# VCA.net
KiCad netlist of a schematic drawn in Altium Designer
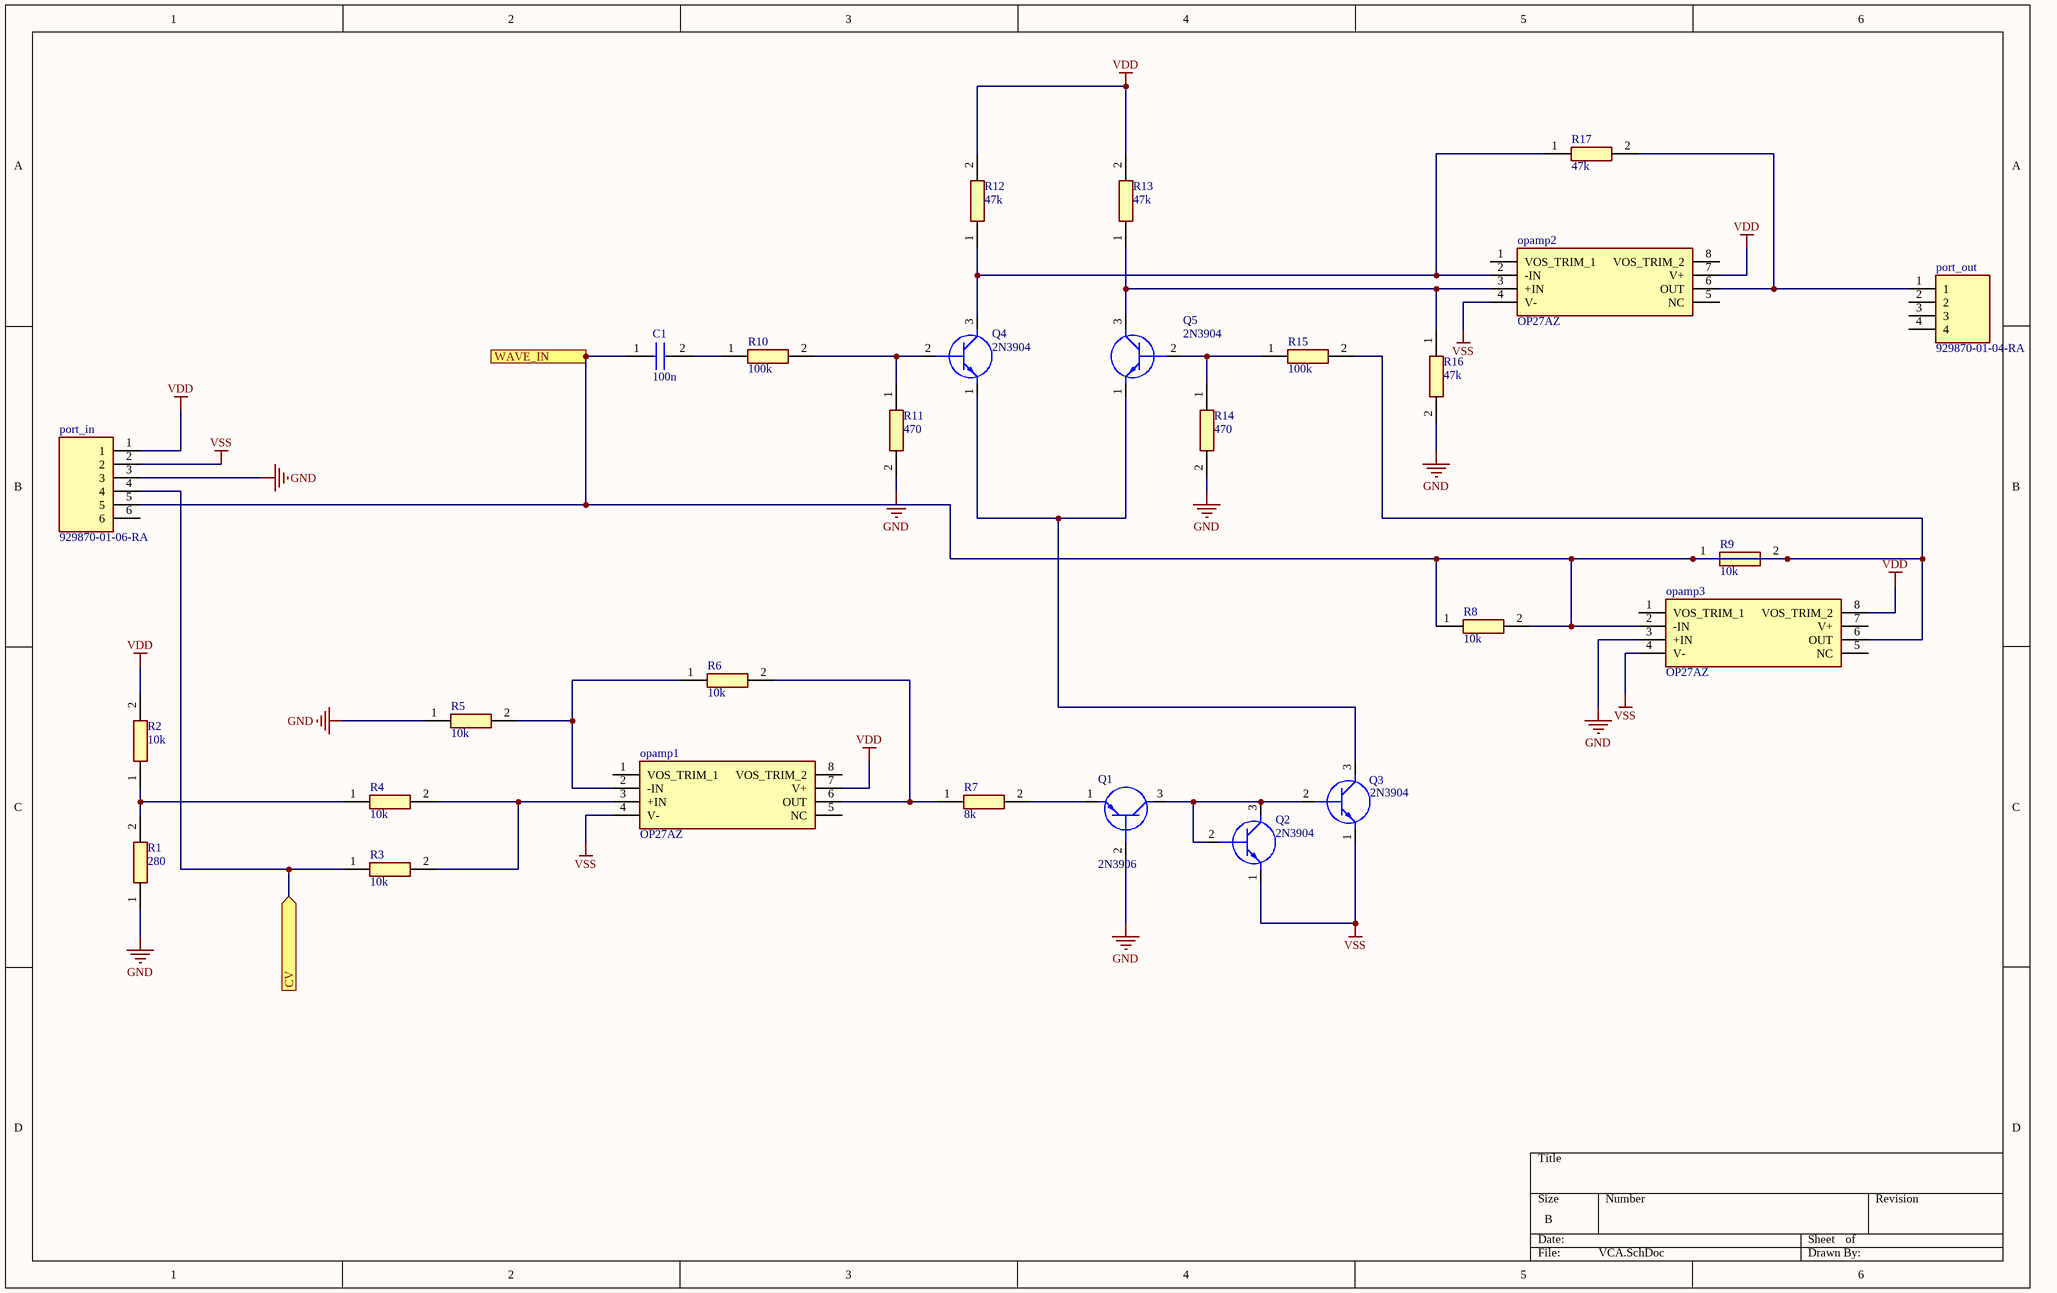
[diagram p0: VCA.SchDoc]

(export (version "E")
  (design (tool "Eeschema 10.0.6"))
  (components
    (comp (ref "C1")
      (value "100n")
      (footprint "SamacSys:CAPPA2400W30L800D400")
      (description "Capacitor")
      (fields (field (name "MANUFACTURER_PART_NUMBER") "0113207"))
      (libsource (lib "SamacSys") (part "0113207"))
    )
    (comp (ref "opamp1")
      (value "OP27AZ")
      (footprint "SamacSys:DIP775W58P254L1029H508Q8N")
      (description "Integrated Circuit")
      (fields (field (name "MOUSER PART NUMBER") "700-OP27AZNR"))
      (libsource (lib "SamacSys") (part "OP27AZ"))
    )
    (comp (ref "opamp2")
      (value "OP27AZ")
      (footprint "SamacSys:DIP775W58P254L1029H508Q8N")
      (description "Integrated Circuit")
      (fields (field (name "MOUSER PART NUMBER") "700-OP27AZNR"))
      (libsource (lib "SamacSys") (part "OP27AZ"))
    )
    (comp (ref "opamp3")
      (value "OP27AZ")
      (footprint "SamacSys:DIP775W58P254L1029H508Q8N")
      (description "Integrated Circuit")
      (fields (field (name "MOUSER PART NUMBER") "700-OP27AZNR"))
      (libsource (lib "SamacSys") (part "OP27AZ"))
    )
    (comp (ref "port_in")
      (value "929870-01-06-RA")
      (footprint "SamacSys:RHDR6W64P0X254_1X6_1524X254X380P")
      (description "Connector")
      (fields (field (name "MOUSER PART NUMBER") "517-929870-01-06-RA"))
      (libsource (lib "SamacSys") (part "929870-01-06-RA"))
    )
    (comp (ref "port_out")
      (value "929870-01-04-RA")
      (footprint "SamacSys:RHDR4W76P0X254_1X4_1016X254X826P")
      (description "Connector")
      (fields (field (name "MOUSER PART NUMBER") "517-929870-01-04-RA"))
      (libsource (lib "SamacSys") (part "929870-01-04-RA"))
    )
    (comp (ref "Q1")
      (value "2N3906")
      (footprint "SamacSys:2N5457")
      (description "Transistor BJT PNP")
      (fields (field (name "MOUSER PART NUMBER") "610-2N3906"))
      (libsource (lib "SamacSys") (part "2N3906"))
    )
    (comp (ref "Q2")
      (value "2N3904")
      (footprint "SamacSys:CS_TO-92")
      (description "Transistor BJT NPN")
      (fields (field (name "MOUSER PART NUMBER") "610-2N3904"))
      (libsource (lib "SamacSys") (part "2N3904"))
    )
    (comp (ref "Q3")
      (value "2N3904")
      (footprint "SamacSys:CS_TO-92")
      (description "Transistor BJT NPN")
      (fields (field (name "MOUSER PART NUMBER") "610-2N3904"))
      (libsource (lib "SamacSys") (part "2N3904"))
    )
    (comp (ref "Q4")
      (value "2N3904")
      (footprint "SamacSys:CS_TO-92")
      (description "Transistor BJT NPN")
      (fields (field (name "MOUSER PART NUMBER") "610-2N3904"))
      (libsource (lib "SamacSys") (part "2N3904"))
    )
    (comp (ref "Q5")
      (value "2N3904")
      (footprint "SamacSys:CS_TO-92")
      (description "Transistor BJT NPN")
      (fields (field (name "MOUSER PART NUMBER") "610-2N3904"))
      (libsource (lib "SamacSys") (part "2N3904"))
    )
    (comp (ref "R1")
      (value "280")
      (footprint "SamacSys:RESAD1650W60L650D250")
      (description "Resistor")
      (fields
        (field (name "MANUFACTURER_PART_NUMBER") "MRS25000C1003FC100")
        (field (name "MOUSER PART NUMBER") "594-MRS25000C1003FC1")
      )
      (libsource (lib "") (part "MRS25000C1003FC100_2"))
    )
    (comp (ref "R2")
      (value "10k")
      (footprint "SamacSys:RESAD1650W60L650D250")
      (description "Resistor")
      (fields
        (field (name "MANUFACTURER_PART_NUMBER") "MRS25000C1003FC100")
        (field (name "MOUSER PART NUMBER") "594-MRS25000C1003FC1")
      )
      (libsource (lib "") (part "MRS25000C1003FC100_2"))
    )
    (comp (ref "R3")
      (value "10k")
      (footprint "SamacSys:RESAD1650W60L650D250")
      (description "Resistor")
      (fields
        (field (name "MANUFACTURER_PART_NUMBER") "MRS25000C1003FC100")
        (field (name "MOUSER PART NUMBER") "594-MRS25000C1003FC1")
      )
      (libsource (lib "SamacSys") (part "MRS25000C1003FC100"))
    )
    (comp (ref "R4")
      (value "10k")
      (footprint "SamacSys:RESAD1650W60L650D250")
      (description "Resistor")
      (fields
        (field (name "MANUFACTURER_PART_NUMBER") "MRS25000C1003FC100")
        (field (name "MOUSER PART NUMBER") "594-MRS25000C1003FC1")
      )
      (libsource (lib "SamacSys") (part "MRS25000C1003FC100"))
    )
    (comp (ref "R5")
      (value "10k")
      (footprint "SamacSys:RESAD1650W60L650D250")
      (description "Resistor")
      (fields
        (field (name "MANUFACTURER_PART_NUMBER") "MRS25000C1003FC100")
        (field (name "MOUSER PART NUMBER") "594-MRS25000C1003FC1")
      )
      (libsource (lib "SamacSys") (part "MRS25000C1003FC100"))
    )
    (comp (ref "R6")
      (value "10k")
      (footprint "SamacSys:RESAD1650W60L650D250")
      (description "Resistor")
      (fields
        (field (name "MANUFACTURER_PART_NUMBER") "MRS25000C1003FC100")
        (field (name "MOUSER PART NUMBER") "594-MRS25000C1003FC1")
      )
      (libsource (lib "SamacSys") (part "MRS25000C1003FC100"))
    )
    (comp (ref "R7")
      (value "8k")
      (footprint "SamacSys:RESAD1650W60L650D250")
      (description "Resistor")
      (fields
        (field (name "MANUFACTURER_PART_NUMBER") "MRS25000C1003FC100")
        (field (name "MOUSER PART NUMBER") "594-MRS25000C1003FC1")
      )
      (libsource (lib "SamacSys") (part "MRS25000C1003FC100"))
    )
    (comp (ref "R8")
      (value "10k")
      (footprint "SamacSys:RESAD1650W60L650D250")
      (description "Resistor")
      (fields
        (field (name "MANUFACTURER_PART_NUMBER") "MRS25000C1003FC100")
        (field (name "MOUSER PART NUMBER") "594-MRS25000C1003FC1")
      )
      (libsource (lib "SamacSys") (part "MRS25000C1003FC100"))
    )
    (comp (ref "R9")
      (value "10k")
      (footprint "SamacSys:RESAD1650W60L650D250")
      (description "Resistor")
      (fields
        (field (name "MANUFACTURER_PART_NUMBER") "MRS25000C1003FC100")
        (field (name "MOUSER PART NUMBER") "594-MRS25000C1003FC1")
      )
      (libsource (lib "SamacSys") (part "MRS25000C1003FC100"))
    )
    (comp (ref "R10")
      (value "100k")
      (footprint "SamacSys:RESAD1650W60L650D250")
      (description "Resistor")
      (fields
        (field (name "MANUFACTURER_PART_NUMBER") "MRS25000C1003FC100")
        (field (name "MOUSER PART NUMBER") "594-MRS25000C1003FC1")
      )
      (libsource (lib "SamacSys") (part "MRS25000C1003FC100"))
    )
    (comp (ref "R11")
      (value "470")
      (footprint "SamacSys:RESAD1650W60L650D250")
      (description "Resistor")
      (fields
        (field (name "MANUFACTURER_PART_NUMBER") "MRS25000C1003FC100")
        (field (name "MOUSER PART NUMBER") "594-MRS25000C1003FC1")
      )
      (libsource (lib "") (part "MRS25000C1003FC100_1"))
    )
    (comp (ref "R12")
      (value "47k")
      (footprint "SamacSys:RESAD1650W60L650D250")
      (description "Resistor")
      (fields
        (field (name "MANUFACTURER_PART_NUMBER") "MRS25000C1003FC100")
        (field (name "MOUSER PART NUMBER") "594-MRS25000C1003FC1")
      )
      (libsource (lib "") (part "MRS25000C1003FC100_2"))
    )
    (comp (ref "R13")
      (value "47k")
      (footprint "SamacSys:RESAD1650W60L650D250")
      (description "Resistor")
      (fields
        (field (name "MANUFACTURER_PART_NUMBER") "MRS25000C1003FC100")
        (field (name "MOUSER PART NUMBER") "594-MRS25000C1003FC1")
      )
      (libsource (lib "") (part "MRS25000C1003FC100_2"))
    )
    (comp (ref "R14")
      (value "470")
      (footprint "SamacSys:RESAD1650W60L650D250")
      (description "Resistor")
      (fields
        (field (name "MANUFACTURER_PART_NUMBER") "MRS25000C1003FC100")
        (field (name "MOUSER PART NUMBER") "594-MRS25000C1003FC1")
      )
      (libsource (lib "") (part "MRS25000C1003FC100_1"))
    )
    (comp (ref "R15")
      (value "100k")
      (footprint "SamacSys:RESAD1650W60L650D250")
      (description "Resistor")
      (fields
        (field (name "MANUFACTURER_PART_NUMBER") "MRS25000C1003FC100")
        (field (name "MOUSER PART NUMBER") "594-MRS25000C1003FC1")
      )
      (libsource (lib "SamacSys") (part "MRS25000C1003FC100"))
    )
    (comp (ref "R16")
      (value "47k")
      (footprint "SamacSys:RESAD1650W60L650D250")
      (description "Resistor")
      (fields
        (field (name "MANUFACTURER_PART_NUMBER") "MRS25000C1003FC100")
        (field (name "MOUSER PART NUMBER") "594-MRS25000C1003FC1")
      )
      (libsource (lib "") (part "MRS25000C1003FC100_1"))
    )
    (comp (ref "R17")
      (value "47k")
      (footprint "SamacSys:RESAD1650W60L650D250")
      (description "Resistor")
      (fields
        (field (name "MANUFACTURER_PART_NUMBER") "MRS25000C1003FC100")
        (field (name "MOUSER PART NUMBER") "594-MRS25000C1003FC1")
      )
      (libsource (lib "SamacSys") (part "MRS25000C1003FC100"))
    )
  )
  (nets
    (net (code "1") (name "/CV") (class "Default")
      (node (ref "R3") (pin "1") (pinfunction "1_1") (pintype "passive"))
      (node (ref "port_in") (pin "4") (pinfunction "4_4") (pintype "passive"))
    )
    (net (code "2") (name "/WAVE_IN") (class "Default")
      (node (ref "C1") (pin "1") (pinfunction "+_1") (pintype "passive"))
      (node (ref "R15") (pin "2") (pinfunction "2_2") (pintype "passive"))
      (node (ref "R8") (pin "1") (pinfunction "1_1") (pintype "passive"))
      (node (ref "R8") (pin "2") (pinfunction "2_2") (pintype "passive"))
      (node (ref "R9") (pin "1") (pinfunction "1_1") (pintype "passive"))
      (node (ref "R9") (pin "2") (pinfunction "2_2") (pintype "passive"))
      (node (ref "opamp3") (pin "2") (pinfunction "-IN_2") (pintype "passive"))
      (node (ref "opamp3") (pin "6") (pinfunction "OUT_6") (pintype "passive"))
      (node (ref "port_in") (pin "5") (pinfunction "5_5") (pintype "passive"))
    )
    (net (code "3") (name "GND") (class "Default")
      (node (ref "Q1") (pin "2") (pinfunction "B_2") (pintype "passive"))
      (node (ref "R1") (pin "1") (pinfunction "1_1") (pintype "passive"))
      (node (ref "R11") (pin "2") (pinfunction "2_2") (pintype "passive"))
      (node (ref "R14") (pin "2") (pinfunction "2_2") (pintype "passive"))
      (node (ref "R16") (pin "2") (pinfunction "2_2") (pintype "passive"))
      (node (ref "R5") (pin "1") (pinfunction "1_1") (pintype "passive"))
      (node (ref "opamp3") (pin "3") (pinfunction "+IN_3") (pintype "passive"))
      (node (ref "port_in") (pin "3") (pinfunction "3_3") (pintype "passive"))
    )
    (net (code "4") (name "Net-(C1--)") (class "Default")
      (node (ref "C1") (pin "2") (pinfunction "-_2") (pintype "passive"))
      (node (ref "R10") (pin "1") (pinfunction "1_1") (pintype "passive"))
    )
    (net (code "5") (name "Net-(Q1-C)") (class "Default")
      (node (ref "Q1") (pin "3") (pinfunction "C_3") (pintype "passive"))
      (node (ref "Q2") (pin "2") (pinfunction "B_2") (pintype "passive"))
      (node (ref "Q2") (pin "3") (pinfunction "C_3") (pintype "passive"))
      (node (ref "Q3") (pin "2") (pinfunction "B_2") (pintype "passive"))
    )
    (net (code "6") (name "Net-(Q1-E)") (class "Default")
      (node (ref "Q1") (pin "1") (pinfunction "E_1") (pintype "passive"))
      (node (ref "R7") (pin "2") (pinfunction "2_2") (pintype "passive"))
    )
    (net (code "7") (name "Net-(Q3-C)") (class "Default")
      (node (ref "Q3") (pin "3") (pinfunction "C_3") (pintype "passive"))
      (node (ref "Q4") (pin "1") (pinfunction "E_1") (pintype "passive"))
      (node (ref "Q5") (pin "1") (pinfunction "E_1") (pintype "passive"))
    )
    (net (code "8") (name "Net-(Q4-B)") (class "Default")
      (node (ref "Q4") (pin "2") (pinfunction "B_2") (pintype "passive"))
      (node (ref "R10") (pin "2") (pinfunction "2_2") (pintype "passive"))
      (node (ref "R11") (pin "1") (pinfunction "1_1") (pintype "passive"))
    )
    (net (code "9") (name "Net-(Q4-C)") (class "Default")
      (node (ref "Q4") (pin "3") (pinfunction "C_3") (pintype "passive"))
      (node (ref "R12") (pin "1") (pinfunction "1_1") (pintype "passive"))
      (node (ref "R17") (pin "1") (pinfunction "1_1") (pintype "passive"))
      (node (ref "opamp2") (pin "2") (pinfunction "-IN_2") (pintype "passive"))
    )
    (net (code "10") (name "Net-(Q5-B)") (class "Default")
      (node (ref "Q5") (pin "2") (pinfunction "B_2") (pintype "passive"))
      (node (ref "R14") (pin "1") (pinfunction "1_1") (pintype "passive"))
      (node (ref "R15") (pin "1") (pinfunction "1_1") (pintype "passive"))
    )
    (net (code "11") (name "Net-(Q5-C)") (class "Default")
      (node (ref "Q5") (pin "3") (pinfunction "C_3") (pintype "passive"))
      (node (ref "R13") (pin "1") (pinfunction "1_1") (pintype "passive"))
      (node (ref "R16") (pin "1") (pinfunction "1_1") (pintype "passive"))
      (node (ref "opamp2") (pin "3") (pinfunction "+IN_3") (pintype "passive"))
    )
    (net (code "12") (name "Net-(R1-Pad2)") (class "Default")
      (node (ref "R1") (pin "2") (pinfunction "2_2") (pintype "passive"))
      (node (ref "R2") (pin "1") (pinfunction "1_1") (pintype "passive"))
      (node (ref "R4") (pin "1") (pinfunction "1_1") (pintype "passive"))
    )
    (net (code "13") (name "Net-(opamp1-+IN)") (class "Default")
      (node (ref "R3") (pin "2") (pinfunction "2_2") (pintype "passive"))
      (node (ref "R4") (pin "2") (pinfunction "2_2") (pintype "passive"))
      (node (ref "opamp1") (pin "3") (pinfunction "+IN_3") (pintype "passive"))
    )
    (net (code "14") (name "Net-(opamp1--IN)") (class "Default")
      (node (ref "R5") (pin "2") (pinfunction "2_2") (pintype "passive"))
      (node (ref "R6") (pin "1") (pinfunction "1_1") (pintype "passive"))
      (node (ref "opamp1") (pin "2") (pinfunction "-IN_2") (pintype "passive"))
    )
    (net (code "15") (name "Net-(opamp1-OUT)") (class "Default")
      (node (ref "R6") (pin "2") (pinfunction "2_2") (pintype "passive"))
      (node (ref "R7") (pin "1") (pinfunction "1_1") (pintype "passive"))
      (node (ref "opamp1") (pin "6") (pinfunction "OUT_6") (pintype "passive"))
    )
    (net (code "16") (name "Net-(opamp2-OUT)") (class "Default")
      (node (ref "R17") (pin "2") (pinfunction "2_2") (pintype "passive"))
      (node (ref "opamp2") (pin "6") (pinfunction "OUT_6") (pintype "passive"))
      (node (ref "port_out") (pin "1") (pinfunction "1_1") (pintype "passive"))
    )
    (net (code "17") (name "VDD") (class "Default")
      (node (ref "R12") (pin "2") (pinfunction "2_2") (pintype "passive"))
      (node (ref "R13") (pin "2") (pinfunction "2_2") (pintype "passive"))
      (node (ref "R2") (pin "2") (pinfunction "2_2") (pintype "passive"))
      (node (ref "opamp1") (pin "7") (pinfunction "V+_7") (pintype "passive"))
      (node (ref "opamp2") (pin "7") (pinfunction "V+_7") (pintype "passive"))
      (node (ref "opamp3") (pin "8") (pinfunction "VOS_TRIM_2_8") (pintype "passive"))
      (node (ref "port_in") (pin "1") (pinfunction "1_1") (pintype "passive"))
    )
    (net (code "18") (name "VSS") (class "Default")
      (node (ref "Q2") (pin "1") (pinfunction "E_1") (pintype "passive"))
      (node (ref "Q3") (pin "1") (pinfunction "E_1") (pintype "passive"))
      (node (ref "opamp1") (pin "4") (pinfunction "V-_4") (pintype "passive"))
      (node (ref "opamp2") (pin "4") (pinfunction "V-_4") (pintype "passive"))
      (node (ref "opamp3") (pin "4") (pinfunction "V-_4") (pintype "passive"))
      (node (ref "port_in") (pin "2") (pinfunction "2_2") (pintype "passive"))
    )
    (net (code "19") (name "unconnected-(opamp1-NC-Pad5)") (class "Default")
      (node (ref "opamp1") (pin "5") (pinfunction "NC_5") (pintype "passive"))
    )
    (net (code "20") (name "unconnected-(opamp1-VOS_TRIM_1-Pad1)") (class "Default")
      (node (ref "opamp1") (pin "1") (pinfunction "VOS_TRIM_1_1") (pintype "passive"))
    )
    (net (code "21") (name "unconnected-(opamp1-VOS_TRIM_2-Pad8)") (class "Default")
      (node (ref "opamp1") (pin "8") (pinfunction "VOS_TRIM_2_8") (pintype "passive"))
    )
    (net (code "22") (name "unconnected-(opamp2-NC-Pad5)") (class "Default")
      (node (ref "opamp2") (pin "5") (pinfunction "NC_5") (pintype "passive"))
    )
    (net (code "23") (name "unconnected-(opamp2-VOS_TRIM_1-Pad1)") (class "Default")
      (node (ref "opamp2") (pin "1") (pinfunction "VOS_TRIM_1_1") (pintype "passive"))
    )
    (net (code "24") (name "unconnected-(opamp2-VOS_TRIM_2-Pad8)") (class "Default")
      (node (ref "opamp2") (pin "8") (pinfunction "VOS_TRIM_2_8") (pintype "passive"))
    )
    (net (code "25") (name "unconnected-(opamp3-NC-Pad5)") (class "Default")
      (node (ref "opamp3") (pin "5") (pinfunction "NC_5") (pintype "passive"))
    )
    (net (code "26") (name "unconnected-(opamp3-V+-Pad7)") (class "Default")
      (node (ref "opamp3") (pin "7") (pinfunction "V+_7") (pintype "passive"))
    )
    (net (code "27") (name "unconnected-(opamp3-VOS_TRIM_1-Pad1)") (class "Default")
      (node (ref "opamp3") (pin "1") (pinfunction "VOS_TRIM_1_1") (pintype "passive"))
    )
    (net (code "28") (name "unconnected-(port_in-Pad6)") (class "Default")
      (node (ref "port_in") (pin "6") (pinfunction "6_6") (pintype "passive"))
    )
    (net (code "29") (name "unconnected-(port_out-Pad2)") (class "Default")
      (node (ref "port_out") (pin "2") (pinfunction "2_2") (pintype "passive"))
    )
    (net (code "30") (name "unconnected-(port_out-Pad3)") (class "Default")
      (node (ref "port_out") (pin "3") (pinfunction "3_3") (pintype "passive"))
    )
    (net (code "31") (name "unconnected-(port_out-Pad4)") (class "Default")
      (node (ref "port_out") (pin "4") (pinfunction "4_4") (pintype "passive"))
    )
  )
)
